# ver_4.net
KiCad netlist of a schematic drawn in Altium Designer
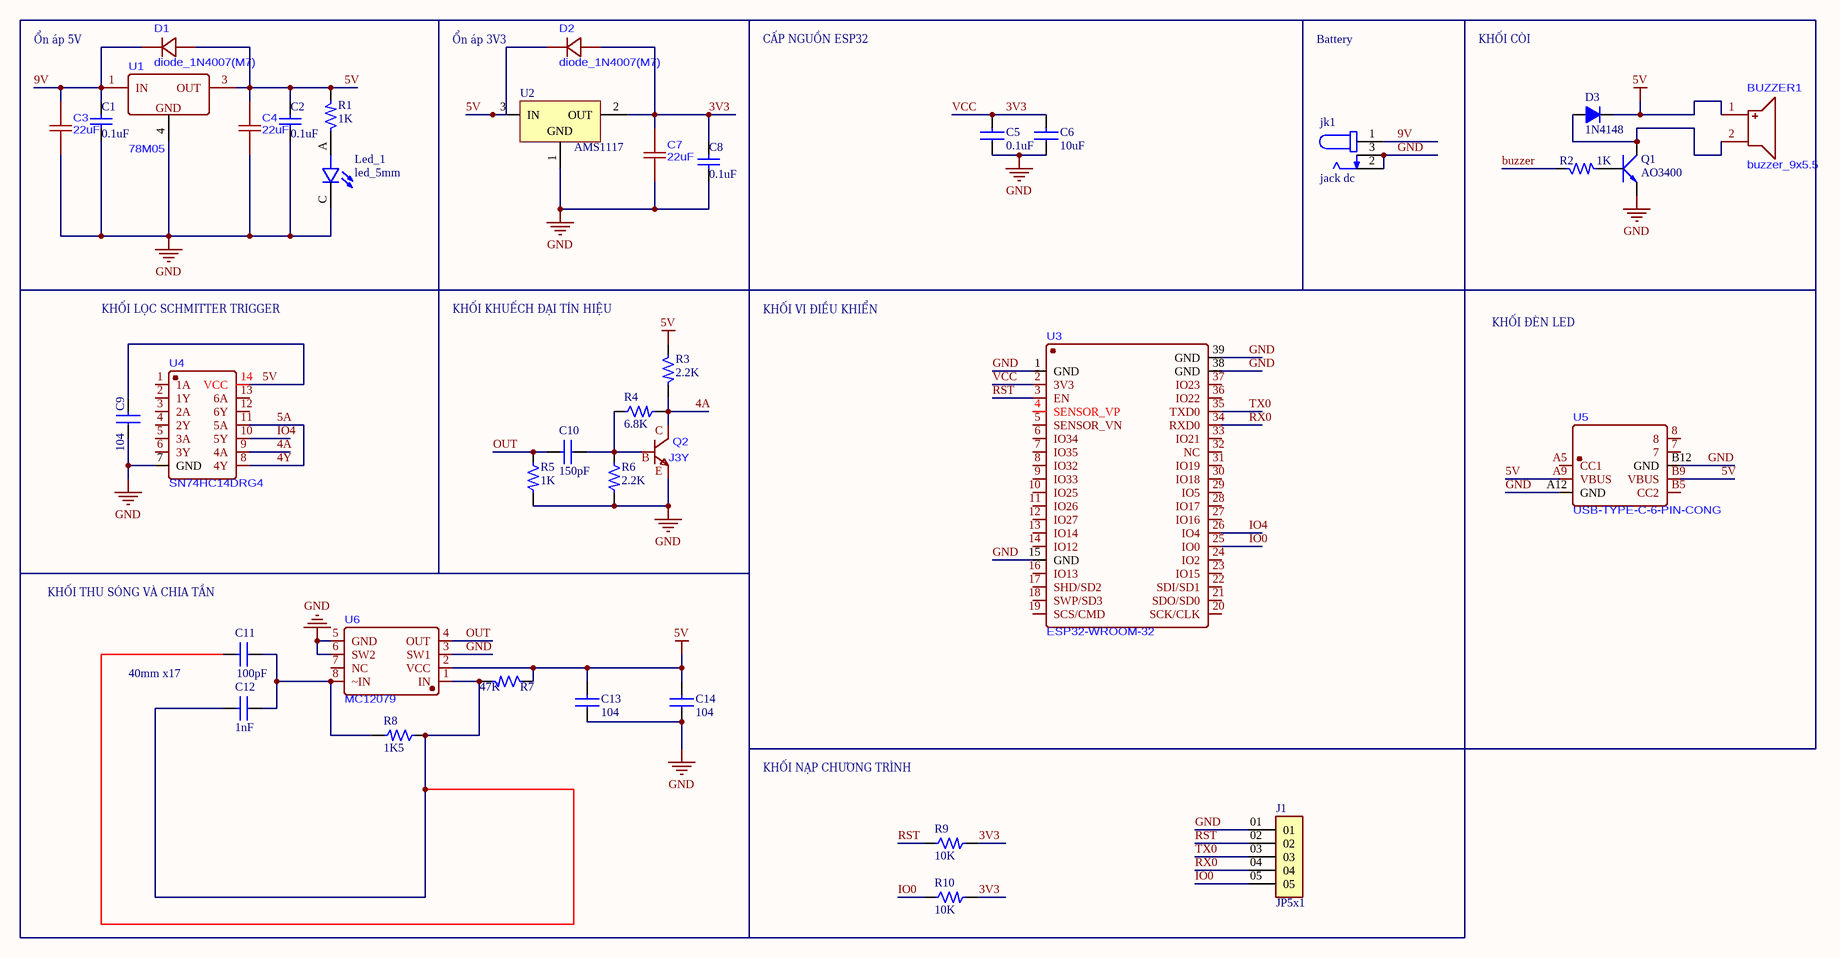
[diagram p0: ver_4.SchDoc]

(export (version "E")
  (design (tool "Eeschema 10.0.6"))
  (components
    (comp (ref "BUZZER1")
      (value "buzzer_9x5.5")
      (footprint "buzzer_9x5.5")
      (libsource (lib "Phong_Cach") (part "buzzer_9x5.5"))
    )
    (comp (ref "C1")
      (value "0.1uF")
      (footprint "CN-SMD-0603")
      (libsource (lib "Thu Vien Chuan MH") (part "CAP 104"))
    )
    (comp (ref "C2")
      (value "0.1uF")
      (footprint "CN-SMD-0603")
      (libsource (lib "Thu Vien Chuan MH") (part "CAP 104"))
    )
    (comp (ref "C3") (value "22uF") (footprint "cap_1206") (libsource (lib "Phong_Cach") (part "cap_1206")))
    (comp (ref "C4") (value "22uF") (footprint "cap_1206") (libsource (lib "Phong_Cach") (part "cap_1206")))
    (comp (ref "C5")
      (value "0.1uF")
      (footprint "CN-SMD-0603")
      (description "Tu 0805")
      (libsource (lib "BLE_ST") (part "Tu 0805_1"))
    )
    (comp (ref "C6")
      (value "10uF")
      (footprint "CN-SMD-0603")
      (description "Tu 0805")
      (libsource (lib "BLE_ST") (part "Tu 0805_1"))
    )
    (comp (ref "C7") (value "22uF") (footprint "cap_1206") (libsource (lib "Phong_Cach") (part "cap_1206")))
    (comp (ref "C8")
      (value "0.1uF")
      (footprint "CN-SMD-0603")
      (libsource (lib "Thu Vien Chuan MH") (part "CAP 104"))
    )
    (comp (ref "C9")
      (value "104")
      (footprint "CN-SMD-0603")
      (description "Tu 0805")
      (libsource (lib "BLE_ST") (part "Tu 0805_1"))
    )
    (comp (ref "C10")
      (value "150pF")
      (footprint "CN-SMD-0603")
      (description "Tu 0805")
      (libsource (lib "BLE_ST") (part "Tu 0805_1"))
    )
    (comp (ref "C11")
      (value "100pF")
      (footprint "CN-SMD-0603")
      (description "Tu 0805")
      (libsource (lib "BLE_ST") (part "Tu 0805_1"))
    )
    (comp (ref "C12")
      (value "1nF")
      (footprint "CN-SMD-0603")
      (description "Tu 0805")
      (libsource (lib "BLE_ST") (part "Tu 0805_1"))
    )
    (comp (ref "C13")
      (value "104")
      (footprint "CN-SMD-0603")
      (description "Tu 0805")
      (libsource (lib "BLE_ST") (part "Tu 0805_1"))
    )
    (comp (ref "C14")
      (value "104")
      (footprint "CN-SMD-0603")
      (description "Tu 0805")
      (libsource (lib "BLE_ST") (part "Tu 0805_1"))
    )
    (comp (ref "D1")
      (value "diode_1N4007(M7)")
      (footprint "diode_1N4007-M7")
      (libsource (lib "Phong_Cach") (part "diode_1N4007(M7)"))
    )
    (comp (ref "D2")
      (value "diode_1N4007(M7)")
      (footprint "diode_1N4007-M7")
      (libsource (lib "Phong_Cach") (part "diode_1N4007(M7)"))
    )
    (comp (ref "D3")
      (value "1N4148")
      (footprint "SOD-123")
      (description "Diode 1A")
      (libsource (lib "syhaunguyen") (part "D1A"))
    )
    (comp (ref "J1") (value "JP5x1") (footprint "JP5x1") (libsource (lib "Phong_Cach") (part "JP5x1")))
    (comp (ref "jk1") (value "jack dc") (footprint "jack dc") (libsource (lib "Phong_Cach") (part "jack dc")))
    (comp (ref "Led_1")
      (value "led_5mm")
      (footprint "led_5mm")
      (libsource (lib "Phong_Cach") (part "led_5mm"))
    )
    (comp (ref "Q1")
      (value "AO3400")
      (footprint "SOT23B")
      (description "NPN 600mW, ECB")
      (libsource (lib "BLE_ST") (part "C1815"))
    )
    (comp (ref "Q2") (value "J3Y") (footprint "j3y") (libsource (lib "Phong_Cach") (part "S8050/J3Y/0.4")))
    (comp (ref "R1")
      (value "1K")
      (footprint "RES-SMD-0603")
      (description "Resistor 1/4W")
      (libsource (lib "BLE_ST") (part "Res"))
    )
    (comp (ref "R2")
      (value "1K")
      (footprint "RES-SMD-0603")
      (description "Resistor 1/4W")
      (libsource (lib "Lib_Chuan_03_08_2013") (part "Res"))
    )
    (comp (ref "R3")
      (value "2.2K")
      (footprint "RES-SMD-0603")
      (description "Tro 0805")
      (libsource (lib "BLE_ST") (part "Tro 0805_1"))
    )
    (comp (ref "R4")
      (value "6.8K")
      (footprint "RES-SMD-0603")
      (description "Tro 0805")
      (libsource (lib "BLE_ST") (part "Tro 0805_1"))
    )
    (comp (ref "R5")
      (value "1K")
      (footprint "RES-SMD-0603")
      (description "Tro 0805")
      (libsource (lib "BLE_ST") (part "Tro 0805_1"))
    )
    (comp (ref "R6")
      (value "2.2K")
      (footprint "RES-SMD-0603")
      (description "Tro 0805")
      (libsource (lib "BLE_ST") (part "Tro 0805_1"))
    )
    (comp (ref "R7")
      (value "47K")
      (footprint "RES-SMD-0603")
      (description "Tro 0805")
      (libsource (lib "BLE_ST") (part "Tro 0805_1"))
    )
    (comp (ref "R8")
      (value "1K5")
      (footprint "RES-SMD-0603")
      (description "Tro 0805")
      (libsource (lib "BLE_ST") (part "Tro 0805_1"))
    )
    (comp (ref "R9")
      (value "10K")
      (footprint "RES-SMD-0603")
      (description "Tro 0805")
      (libsource (lib "BLE_ST") (part "Tro 0805_1"))
    )
    (comp (ref "R10")
      (value "10K")
      (footprint "RES-SMD-0603")
      (description "Tro 0805")
      (libsource (lib "BLE_ST") (part "Tro 0805_1"))
    )
    (comp (ref "U1") (value "78M05") (footprint "78M05") (libsource (lib "Phong_Cach") (part "78M05")))
    (comp (ref "U2")
      (value "AMS1117")
      (footprint "AMS1117-SOT223")
      (libsource (lib "QT TECH CO.,LTD") (part "AMS1117"))
    )
    (comp (ref "U3")
      (value "ESP32-WROOM-32")
      (footprint "ESP-32-WROOM")
      (libsource (lib "Phong_Cach") (part "ESP32-WROOM-32"))
    )
    (comp (ref "U4")
      (value "SN74HC14DRG4")
      (footprint "74HC14")
      (libsource (lib "Phong_Cach") (part "SN74HC14DRG4"))
    )
    (comp (ref "U5")
      (value "USB-TYPE-C-6-PIN-CONG")
      (footprint "USB-TYPE-C-6-PIN-CONG")
      (libsource (lib "Phong_Cach") (part "USB-TYPE-C-6-PIN-CONG"))
    )
    (comp (ref "U6") (value "MC12079") (footprint "MC12079") (libsource (lib "Phong_Cach") (part "MC12079")))
  )
  (nets
    (net (code "1") (name "/3V3") (class "Default")
      (node (ref "C5") (pin "2") (pinfunction "2_2") (pintype "passive"))
      (node (ref "C6") (pin "2") (pinfunction "2_2") (pintype "passive"))
      (node (ref "C7") (pin "2") (pinfunction "2_2") (pintype "passive"))
      (node (ref "C8") (pin "2") (pinfunction "2_2") (pintype "passive"))
      (node (ref "D2") (pin "2") (pinfunction "A_2") (pintype "passive"))
      (node (ref "R10") (pin "2") (pinfunction "2_2") (pintype "passive"))
      (node (ref "R9") (pin "2") (pinfunction "2_2") (pintype "passive"))
      (node (ref "U2") (pin "2") (pinfunction "OUT_2") (pintype "power_in"))
      (node (ref "U3") (pin "2") (pinfunction "3V3_2") (pintype "passive"))
    )
    (net (code "2") (name "/4A") (class "Default")
      (node (ref "Q2") (pin "3") (pinfunction "C_3") (pintype "passive"))
      (node (ref "R3") (pin "2") (pinfunction "2_2") (pintype "passive"))
      (node (ref "R4") (pin "2") (pinfunction "2_2") (pintype "passive"))
      (node (ref "U4") (pin "9") (pinfunction "4A_9") (pintype "passive"))
    )
    (net (code "3") (name "/4Y") (class "Default")
      (node (ref "U4") (pin "11") (pinfunction "5A_11") (pintype "passive"))
      (node (ref "U4") (pin "8") (pinfunction "4Y_8") (pintype "passive"))
    )
    (net (code "4") (name "/9V") (class "Default")
      (node (ref "C1") (pin "2") (pinfunction "2_2") (pintype "passive"))
      (node (ref "C3") (pin "2") (pinfunction "2_2") (pintype "passive"))
      (node (ref "D1") (pin "1") (pinfunction "K_1") (pintype "passive"))
      (node (ref "U1") (pin "1") (pinfunction "IN_1") (pintype "passive"))
      (node (ref "jk1") (pin "1") (pinfunction "1_1") (pintype "passive"))
    )
    (net (code "5") (name "/IO0") (class "Default")
      (node (ref "J1") (pin "05") (pinfunction "05_05") (pintype "passive"))
      (node (ref "R10") (pin "1") (pinfunction "1_1") (pintype "passive"))
      (node (ref "U3") (pin "25") (pinfunction "IO0_25") (pintype "passive"))
    )
    (net (code "6") (name "/IO4") (class "Default")
      (node (ref "U3") (pin "26") (pinfunction "IO4_26") (pintype "passive"))
      (node (ref "U4") (pin "10") (pinfunction "5Y_10") (pintype "passive"))
    )
    (net (code "7") (name "/OUT") (class "Default")
      (node (ref "C10") (pin "2") (pinfunction "2_2") (pintype "passive"))
      (node (ref "R5") (pin "1") (pinfunction "1_1") (pintype "passive"))
      (node (ref "U6") (pin "4") (pinfunction "OUT_4") (pintype "passive"))
    )
    (net (code "8") (name "/RST") (class "Default")
      (node (ref "J1") (pin "02") (pinfunction "02_02") (pintype "passive"))
      (node (ref "R9") (pin "1") (pinfunction "1_1") (pintype "passive"))
      (node (ref "U3") (pin "3") (pinfunction "EN_3") (pintype "passive"))
    )
    (net (code "9") (name "/RX0") (class "Default")
      (node (ref "J1") (pin "04") (pinfunction "04_04") (pintype "passive"))
      (node (ref "U3") (pin "34") (pinfunction "RXD0_34") (pintype "passive"))
    )
    (net (code "10") (name "/TX0") (class "Default")
      (node (ref "J1") (pin "03") (pinfunction "03_03") (pintype "passive"))
      (node (ref "U3") (pin "35") (pinfunction "TXD0_35") (pintype "passive"))
    )
    (net (code "11") (name "/buzzer") (class "Default")
      (node (ref "R2") (pin "1") (pinfunction "1_1") (pintype "passive"))
    )
    (net (code "12") (name "5V") (class "Default")
      (node (ref "BUZZER1") (pin "1") (pinfunction "1_1") (pintype "passive"))
      (node (ref "C13") (pin "2") (pinfunction "2_2") (pintype "passive"))
      (node (ref "C14") (pin "2") (pinfunction "2_2") (pintype "passive"))
      (node (ref "C2") (pin "2") (pinfunction "2_2") (pintype "passive"))
      (node (ref "C4") (pin "2") (pinfunction "2_2") (pintype "passive"))
      (node (ref "C9") (pin "2") (pinfunction "2_2") (pintype "passive"))
      (node (ref "D1") (pin "2") (pinfunction "A_2") (pintype "passive"))
      (node (ref "D2") (pin "1") (pinfunction "K_1") (pintype "passive"))
      (node (ref "D3") (pin "2") (pinfunction "K_2") (pintype "passive"))
      (node (ref "R1") (pin "2") (pinfunction "2_2") (pintype "passive"))
      (node (ref "R3") (pin "1") (pinfunction "1_1") (pintype "passive"))
      (node (ref "R7") (pin "1") (pinfunction "1_1") (pintype "passive"))
      (node (ref "U1") (pin "3") (pinfunction "OUT_3") (pintype "passive"))
      (node (ref "U2") (pin "3") (pinfunction "IN_3") (pintype "power_in"))
      (node (ref "U4") (pin "14") (pinfunction "VCC_14") (pintype "passive"))
      (node (ref "U5") (pin "A9") (pinfunction "VBUS_A9") (pintype "passive"))
      (node (ref "U5") (pin "B9") (pinfunction "VBUS_B9") (pintype "passive"))
      (node (ref "U6") (pin "2") (pinfunction "VCC_2") (pintype "passive"))
    )
    (net (code "13") (name "GND") (class "Default")
      (node (ref "C1") (pin "1") (pinfunction "1_1") (pintype "passive"))
      (node (ref "C13") (pin "1") (pinfunction "1_1") (pintype "passive"))
      (node (ref "C14") (pin "1") (pinfunction "1_1") (pintype "passive"))
      (node (ref "C2") (pin "1") (pinfunction "1_1") (pintype "passive"))
      (node (ref "C3") (pin "1") (pinfunction "1_1") (pintype "passive"))
      (node (ref "C4") (pin "1") (pinfunction "1_1") (pintype "passive"))
      (node (ref "C5") (pin "1") (pinfunction "1_1") (pintype "passive"))
      (node (ref "C6") (pin "1") (pinfunction "1_1") (pintype "passive"))
      (node (ref "C7") (pin "1") (pinfunction "1_1") (pintype "passive"))
      (node (ref "C8") (pin "1") (pinfunction "1_1") (pintype "passive"))
      (node (ref "C9") (pin "1") (pinfunction "1_1") (pintype "passive"))
      (node (ref "J1") (pin "01") (pinfunction "01_01") (pintype "passive"))
      (node (ref "Led_1") (pin "C") (pinfunction "C_C") (pintype "passive"))
      (node (ref "Q1") (pin "1") (pinfunction "E_1") (pintype "passive"))
      (node (ref "Q2") (pin "2") (pinfunction "E_2") (pintype "passive"))
      (node (ref "R5") (pin "2") (pinfunction "2_2") (pintype "passive"))
      (node (ref "R6") (pin "2") (pinfunction "2_2") (pintype "passive"))
      (node (ref "U1") (pin "4") (pinfunction "GND_4") (pintype "passive"))
      (node (ref "U2") (pin "1") (pinfunction "GND_1") (pintype "power_in"))
      (node (ref "U3") (pin "1") (pinfunction "GND_1") (pintype "passive"))
      (node (ref "U3") (pin "15") (pinfunction "GND_15") (pintype "passive"))
      (node (ref "U3") (pin "38") (pinfunction "GND_38") (pintype "passive"))
      (node (ref "U3") (pin "39") (pinfunction "GND_39") (pintype "passive"))
      (node (ref "U4") (pin "7") (pinfunction "GND_7") (pintype "passive"))
      (node (ref "U5") (pin "A12") (pinfunction "GND_A12") (pintype "passive"))
      (node (ref "U5") (pin "B12") (pinfunction "GND_B12") (pintype "passive"))
      (node (ref "U6") (pin "3") (pinfunction "SW1_3") (pintype "passive"))
      (node (ref "U6") (pin "5") (pinfunction "GND_5") (pintype "passive"))
      (node (ref "U6") (pin "6") (pinfunction "SW2_6") (pintype "passive"))
      (node (ref "jk1") (pin "2") (pinfunction "2_2") (pintype "passive"))
      (node (ref "jk1") (pin "3") (pinfunction "3_3") (pintype "passive"))
    )
    (net (code "14") (name "Net-(D3-A)") (class "Default")
      (node (ref "BUZZER1") (pin "2") (pinfunction "2_2") (pintype "passive"))
      (node (ref "D3") (pin "1") (pinfunction "A_1") (pintype "passive"))
      (node (ref "Q1") (pin "2") (pinfunction "C_2") (pintype "passive"))
    )
    (net (code "15") (name "Net-(Led_1-PadA)") (class "Default")
      (node (ref "Led_1") (pin "A") (pinfunction "A_A") (pintype "passive"))
      (node (ref "R1") (pin "1") (pinfunction "1_1") (pintype "passive"))
    )
    (net (code "16") (name "Net-(Q1-B)") (class "Default")
      (node (ref "Q1") (pin "3") (pinfunction "B_3") (pintype "passive"))
      (node (ref "R2") (pin "2") (pinfunction "2_2") (pintype "passive"))
    )
    (net (code "17") (name "Net-(Q2-B)") (class "Default")
      (node (ref "C10") (pin "1") (pinfunction "1_1") (pintype "passive"))
      (node (ref "Q2") (pin "1") (pinfunction "B_1") (pintype "passive"))
      (node (ref "R4") (pin "1") (pinfunction "1_1") (pintype "passive"))
      (node (ref "R6") (pin "1") (pinfunction "1_1") (pintype "passive"))
    )
    (net (code "18") (name "Net-(U6-IN)") (class "Default")
      (node (ref "C11") (pin "2") (pinfunction "2_2") (pintype "passive"))
      (node (ref "C12") (pin "2") (pinfunction "2_2") (pintype "passive"))
      (node (ref "R7") (pin "2") (pinfunction "2_2") (pintype "passive"))
      (node (ref "R8") (pin "1") (pinfunction "1_1") (pintype "passive"))
      (node (ref "U6") (pin "1") (pinfunction "IN_1") (pintype "passive"))
    )
    (net (code "19") (name "Net-(U6-~IN)") (class "Default")
      (node (ref "C11") (pin "1") (pinfunction "1_1") (pintype "passive"))
      (node (ref "C12") (pin "1") (pinfunction "1_1") (pintype "passive"))
      (node (ref "R8") (pin "2") (pinfunction "2_2") (pintype "passive"))
      (node (ref "U6") (pin "8") (pinfunction "~IN_8") (pintype "passive"))
    )
    (net (code "20") (name "unconnected-(U3-IO2-Pad24)") (class "Default")
      (node (ref "U3") (pin "24") (pinfunction "IO2_24") (pintype "passive"))
    )
    (net (code "21") (name "unconnected-(U3-IO5-Pad29)") (class "Default")
      (node (ref "U3") (pin "29") (pinfunction "IO5_29") (pintype "passive"))
    )
    (net (code "22") (name "unconnected-(U3-IO12-Pad14)") (class "Default")
      (node (ref "U3") (pin "14") (pinfunction "IO12_14") (pintype "passive"))
    )
    (net (code "23") (name "unconnected-(U3-IO13-Pad16)") (class "Default")
      (node (ref "U3") (pin "16") (pinfunction "IO13_16") (pintype "passive"))
    )
    (net (code "24") (name "unconnected-(U3-IO14-Pad13)") (class "Default")
      (node (ref "U3") (pin "13") (pinfunction "IO14_13") (pintype "passive"))
    )
    (net (code "25") (name "unconnected-(U3-IO15-Pad23)") (class "Default")
      (node (ref "U3") (pin "23") (pinfunction "IO15_23") (pintype "passive"))
    )
    (net (code "26") (name "unconnected-(U3-IO16-Pad27)") (class "Default")
      (node (ref "U3") (pin "27") (pinfunction "IO16_27") (pintype "passive"))
    )
    (net (code "27") (name "unconnected-(U3-IO17-Pad28)") (class "Default")
      (node (ref "U3") (pin "28") (pinfunction "IO17_28") (pintype "passive"))
    )
    (net (code "28") (name "unconnected-(U3-IO18-Pad30)") (class "Default")
      (node (ref "U3") (pin "30") (pinfunction "IO18_30") (pintype "passive"))
    )
    (net (code "29") (name "unconnected-(U3-IO19-Pad31)") (class "Default")
      (node (ref "U3") (pin "31") (pinfunction "IO19_31") (pintype "passive"))
    )
    (net (code "30") (name "unconnected-(U3-IO21-Pad33)") (class "Default")
      (node (ref "U3") (pin "33") (pinfunction "IO21_33") (pintype "passive"))
    )
    (net (code "31") (name "unconnected-(U3-IO22-Pad36)") (class "Default")
      (node (ref "U3") (pin "36") (pinfunction "IO22_36") (pintype "passive"))
    )
    (net (code "32") (name "unconnected-(U3-IO23-Pad37)") (class "Default")
      (node (ref "U3") (pin "37") (pinfunction "IO23_37") (pintype "passive"))
    )
    (net (code "33") (name "unconnected-(U3-IO25-Pad10)") (class "Default")
      (node (ref "U3") (pin "10") (pinfunction "IO25_10") (pintype "passive"))
    )
    (net (code "34") (name "unconnected-(U3-IO26-Pad11)") (class "Default")
      (node (ref "U3") (pin "11") (pinfunction "IO26_11") (pintype "passive"))
    )
    (net (code "35") (name "unconnected-(U3-IO27-Pad12)") (class "Default")
      (node (ref "U3") (pin "12") (pinfunction "IO27_12") (pintype "passive"))
    )
    (net (code "36") (name "unconnected-(U3-IO32-Pad8)") (class "Default")
      (node (ref "U3") (pin "8") (pinfunction "IO32_8") (pintype "passive"))
    )
    (net (code "37") (name "unconnected-(U3-IO33-Pad9)") (class "Default")
      (node (ref "U3") (pin "9") (pinfunction "IO33_9") (pintype "passive"))
    )
    (net (code "38") (name "unconnected-(U3-IO34-Pad6)") (class "Default")
      (node (ref "U3") (pin "6") (pinfunction "IO34_6") (pintype "passive"))
    )
    (net (code "39") (name "unconnected-(U3-IO35-Pad7)") (class "Default")
      (node (ref "U3") (pin "7") (pinfunction "IO35_7") (pintype "passive"))
    )
    (net (code "40") (name "unconnected-(U3-NC-Pad32)") (class "Default")
      (node (ref "U3") (pin "32") (pinfunction "NC_32") (pintype "passive"))
    )
    (net (code "41") (name "unconnected-(U3-SCK{slash}CLK-Pad20)") (class "Default")
      (node (ref "U3") (pin "20") (pinfunction "SCK/CLK_20") (pintype "passive"))
    )
    (net (code "42") (name "unconnected-(U3-SCS{slash}CMD-Pad19)") (class "Default")
      (node (ref "U3") (pin "19") (pinfunction "SCS/CMD_19") (pintype "passive"))
    )
    (net (code "43") (name "unconnected-(U3-SDI{slash}SD1-Pad22)") (class "Default")
      (node (ref "U3") (pin "22") (pinfunction "SDI/SD1_22") (pintype "passive"))
    )
    (net (code "44") (name "unconnected-(U3-SDO{slash}SD0-Pad21)") (class "Default")
      (node (ref "U3") (pin "21") (pinfunction "SDO/SD0_21") (pintype "passive"))
    )
    (net (code "45") (name "unconnected-(U3-SENSOR_VN-Pad5)") (class "Default")
      (node (ref "U3") (pin "5") (pinfunction "SENSOR_VN_5") (pintype "passive"))
    )
    (net (code "46") (name "unconnected-(U3-SENSOR_VP-Pad4)") (class "Default")
      (node (ref "U3") (pin "4") (pinfunction "SENSOR_VP_4") (pintype "passive"))
    )
    (net (code "47") (name "unconnected-(U3-SHD{slash}SD2-Pad17)") (class "Default")
      (node (ref "U3") (pin "17") (pinfunction "SHD/SD2_17") (pintype "passive"))
    )
    (net (code "48") (name "unconnected-(U3-SWP{slash}SD3-Pad18)") (class "Default")
      (node (ref "U3") (pin "18") (pinfunction "SWP/SD3_18") (pintype "passive"))
    )
    (net (code "49") (name "unconnected-(U4-1A-Pad1)") (class "Default")
      (node (ref "U4") (pin "1") (pinfunction "1A_1") (pintype "passive"))
    )
    (net (code "50") (name "unconnected-(U4-1Y-Pad2)") (class "Default")
      (node (ref "U4") (pin "2") (pinfunction "1Y_2") (pintype "passive"))
    )
    (net (code "51") (name "unconnected-(U4-2A-Pad3)") (class "Default")
      (node (ref "U4") (pin "3") (pinfunction "2A_3") (pintype "passive"))
    )
    (net (code "52") (name "unconnected-(U4-2Y-Pad4)") (class "Default")
      (node (ref "U4") (pin "4") (pinfunction "2Y_4") (pintype "passive"))
    )
    (net (code "53") (name "unconnected-(U4-3A-Pad5)") (class "Default")
      (node (ref "U4") (pin "5") (pinfunction "3A_5") (pintype "passive"))
    )
    (net (code "54") (name "unconnected-(U4-3Y-Pad6)") (class "Default")
      (node (ref "U4") (pin "6") (pinfunction "3Y_6") (pintype "passive"))
    )
    (net (code "55") (name "unconnected-(U4-6A-Pad13)") (class "Default")
      (node (ref "U4") (pin "13") (pinfunction "6A_13") (pintype "passive"))
    )
    (net (code "56") (name "unconnected-(U4-6Y-Pad12)") (class "Default")
      (node (ref "U4") (pin "12") (pinfunction "6Y_12") (pintype "passive"))
    )
    (net (code "57") (name "unconnected-(U5-CC1-PadA5)") (class "Default")
      (node (ref "U5") (pin "A5") (pinfunction "CC1_A5") (pintype "passive"))
    )
    (net (code "58") (name "unconnected-(U5-CC2-PadB5)") (class "Default")
      (node (ref "U5") (pin "B5") (pinfunction "CC2_B5") (pintype "passive"))
    )
    (net (code "59") (name "unconnected-(U5-Pad7)") (class "Default")
      (node (ref "U5") (pin "7") (pinfunction "7_7") (pintype "passive"))
    )
    (net (code "60") (name "unconnected-(U5-Pad8)") (class "Default")
      (node (ref "U5") (pin "8") (pinfunction "8_8") (pintype "passive"))
    )
    (net (code "61") (name "unconnected-(U6-NC-Pad7)") (class "Default")
      (node (ref "U6") (pin "7") (pinfunction "NC_7") (pintype "passive"))
    )
  )
)
